# mcu.net
KiCad netlist of a schematic drawn in Altium Designer
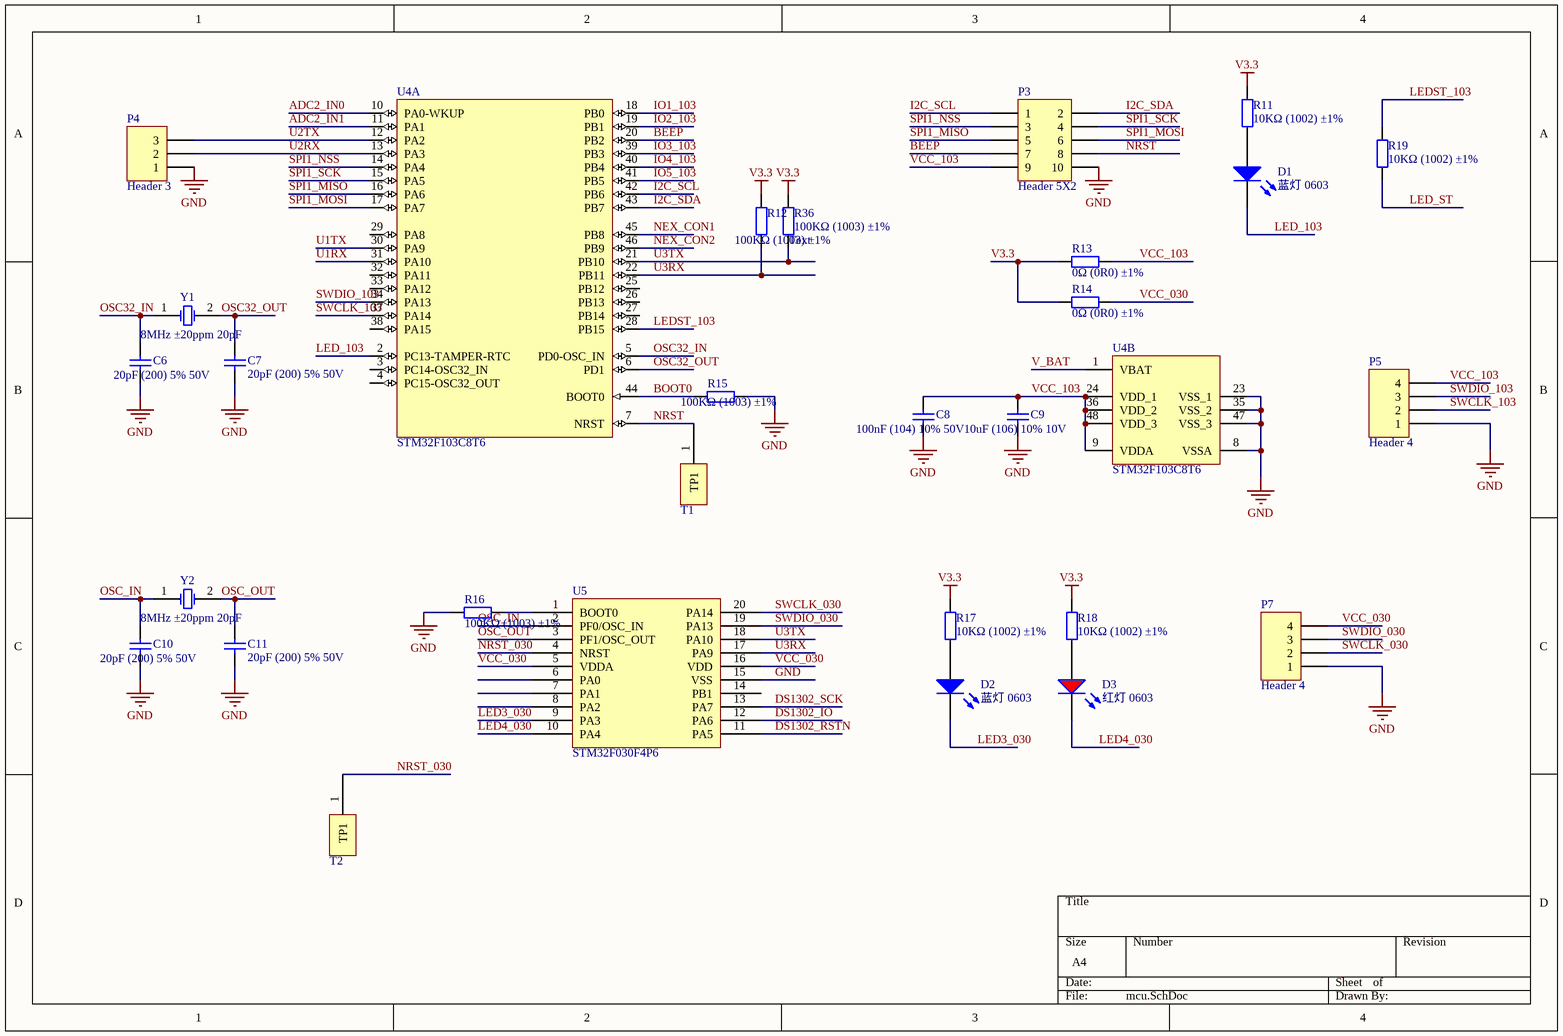
[diagram p0: mcu.SchDoc]

(export (version "E")
  (design (tool "Eeschema 10.0.6"))
  (components
    (comp (ref "C6")
      (value "20pF (200) 5% 50V")
      (footprint "0603_C")
      (description "贴片电容")
      (libsource (lib "Miscellaneous Devices LC") (part "0603 20pF (200) 5% 50V"))
    )
    (comp (ref "C7")
      (value "20pF (200) 5% 50V")
      (footprint "0603_C")
      (description "贴片电容")
      (libsource (lib "Miscellaneous Devices LC") (part "0603 20pF (200) 5% 50V"))
    )
    (comp (ref "C8")
      (value "100nF (104) 10% 50V")
      (footprint "0603_C")
      (description "贴片电容")
      (libsource (lib "Miscellaneous Devices LC") (part "0603 100nF (104) 10% 50V"))
    )
    (comp (ref "C9")
      (value "10uF (106) 10% 10V")
      (footprint "0603_C")
      (description "贴片电容")
      (libsource (lib "Miscellaneous Devices LC") (part "0603 10uF (106) 10% 10V"))
    )
    (comp (ref "C10")
      (value "20pF (200) 5% 50V")
      (footprint "0603_C")
      (description "贴片电容")
      (libsource (lib "Miscellaneous Devices LC") (part "0603 20pF (200) 5% 50V"))
    )
    (comp (ref "C11")
      (value "20pF (200) 5% 50V")
      (footprint "0603_C")
      (description "贴片电容")
      (libsource (lib "Miscellaneous Devices LC") (part "0603 20pF (200) 5% 50V"))
    )
    (comp (ref "D1")
      (value "蓝灯 0603")
      (footprint "0603_LED_S1")
      (description "发光二极管")
      (libsource (lib "Miscellaneous Devices LC") (part "0603 蓝灯"))
    )
    (comp (ref "D2")
      (value "蓝灯 0603")
      (footprint "0603_LED_S1")
      (description "发光二极管")
      (libsource (lib "Miscellaneous Devices LC") (part "0603 蓝灯"))
    )
    (comp (ref "D3")
      (value "红灯 0603")
      (footprint "0603_LED_S1")
      (description "发光二极管")
      (libsource (lib "Miscellaneous Devices LC") (part "0603 红灯"))
    )
    (comp (ref "P3")
      (value "Header 5X2")
      (footprint "HDR2X5")
      (description "Header, 5-Pin, Dual row")
      (fields (field (name "PUBLISHER") "Altium Limited"))
      (libsource (lib "Miscellaneous Connectors") (part "Header 5X2"))
    )
    (comp (ref "P4")
      (value "Header 3")
      (footprint "HDR1X3")
      (description "Header, 3-Pin")
      (fields (field (name "PUBLISHER") "Altium Limited"))
      (libsource (lib "Miscellaneous Connectors") (part "Header 3"))
    )
    (comp (ref "P5")
      (value "Header 4")
      (footprint "HDR1X4")
      (description "Header, 4-Pin")
      (fields (field (name "PUBLISHER") "Altium Limited"))
      (libsource (lib "Miscellaneous Connectors") (part "Header 4"))
    )
    (comp (ref "P7")
      (value "Header 4")
      (footprint "HDR1X4")
      (description "Header, 4-Pin")
      (fields (field (name "PUBLISHER") "Altium Limited"))
      (libsource (lib "Miscellaneous Connectors") (part "Header 4"))
    )
    (comp (ref "R11")
      (value "10KΩ (1002) ±1%")
      (footprint "0603_R")
      (description "贴片电阻")
      (libsource (lib "Miscellaneous Devices LC") (part "0603 10KΩ (1002) 1%"))
    )
    (comp (ref "R12")
      (value "100KΩ (1003) ±1%")
      (footprint "0603_R")
      (description "贴片电阻")
      (libsource (lib "") (part "0603 100KΩ (1003) 1%_1"))
    )
    (comp (ref "R13")
      (value "0Ω (0R0) ±1%")
      (footprint "1206_R")
      (description "贴片电阻")
      (libsource (lib "Miscellaneous Devices LC") (part "1206 0Ω (0R0) 1%"))
    )
    (comp (ref "R14")
      (value "0Ω (0R0) ±1%")
      (footprint "1206_R")
      (description "贴片电阻")
      (libsource (lib "Miscellaneous Devices LC") (part "1206 0Ω (0R0) 1%"))
    )
    (comp (ref "R15")
      (value "100KΩ (1003) ±1%")
      (footprint "0603_R")
      (description "贴片电阻")
      (libsource (lib "Miscellaneous Devices LC") (part "0603 100KΩ (1003) 1%"))
    )
    (comp (ref "R16")
      (value "100KΩ (1003) ±1%")
      (footprint "0603_R")
      (description "贴片电阻")
      (libsource (lib "Miscellaneous Devices LC") (part "0603 100KΩ (1003) 1%"))
    )
    (comp (ref "R17")
      (value "10KΩ (1002) ±1%")
      (footprint "0603_R")
      (description "贴片电阻")
      (libsource (lib "Miscellaneous Devices LC") (part "0603 10KΩ (1002) 1%"))
    )
    (comp (ref "R18")
      (value "10KΩ (1002) ±1%")
      (footprint "0603_R")
      (description "贴片电阻")
      (libsource (lib "Miscellaneous Devices LC") (part "0603 10KΩ (1002) 1%"))
    )
    (comp (ref "R19")
      (value "10KΩ (1002) ±1%")
      (footprint "0603_R")
      (description "贴片电阻")
      (libsource (lib "Miscellaneous Devices LC") (part "0603 10KΩ (1002) 1%"))
    )
    (comp (ref "R36")
      (value "100KΩ (1003) ±1%")
      (footprint "0603_R")
      (description "贴片电阻")
      (libsource (lib "") (part "0603 100KΩ (1003) 1%_1"))
    )
    (comp (ref "T1") (value "TP1") (footprint "TP1") (libsource (lib "CHK-I") (part "TP1")))
    (comp (ref "T2") (value "TP1") (footprint "TP1") (libsource (lib "CHK-I") (part "TP1")))
    (comp (ref "U4")
      (value "STM32F103C8T6")
      (footprint "LQFP-48_7x7x05P")
      (description "ARM")
      (libsource (lib "Miscellaneous Devices LC") (part "STM32F103C8T6"))
    )
    (comp (ref "U5")
      (value "STM32F030F4P6")
      (footprint "TSSOP-20")
      (description "ARM")
      (libsource (lib "Miscellaneous Devices LC") (part "STM32F030F4P6"))
    )
    (comp (ref "Y1")
      (value "8MHz ±20ppm 20pF")
      (footprint "SMD-5032_2P")
      (description "贴片晶振")
      (libsource (lib "Miscellaneous Devices LC") (part "SMD-5032_2P 8MHz 20ppm 20pF"))
    )
    (comp (ref "Y2")
      (value "8MHz ±20ppm 20pF")
      (footprint "SMD-5032_2P")
      (description "贴片晶振")
      (libsource (lib "Miscellaneous Devices LC") (part "SMD-5032_2P 8MHz 20ppm 20pF"))
    )
  )
  (nets
    (net (code "1") (name "/ADC2_IN0") (class "Default")
      (node (ref "U4") (pin "10") (pinfunction "PA0-WKUP_10") (pintype "bidirectional"))
    )
    (net (code "2") (name "/ADC2_IN1") (class "Default")
      (node (ref "U4") (pin "11") (pinfunction "PA1_11") (pintype "bidirectional"))
    )
    (net (code "3") (name "/BEEP") (class "Default")
      (node (ref "P3") (pin "7") (pinfunction "7_7") (pintype "passive"))
      (node (ref "U4") (pin "20") (pinfunction "PB2_20") (pintype "bidirectional"))
    )
    (net (code "4") (name "/BOOT0") (class "Default")
      (node (ref "R15") (pin "1") (pinfunction "1_1") (pintype "passive"))
      (node (ref "U4") (pin "44") (pinfunction "BOOT0_44") (pintype "input"))
    )
    (net (code "5") (name "/DS1302_IO") (class "Default")
      (node (ref "U5") (pin "12") (pinfunction "PA6_12") (pintype "passive"))
    )
    (net (code "6") (name "/DS1302_RSTN") (class "Default")
      (node (ref "U5") (pin "11") (pinfunction "PA5_11") (pintype "passive"))
    )
    (net (code "7") (name "/DS1302_SCK") (class "Default")
      (node (ref "U5") (pin "13") (pinfunction "PA7_13") (pintype "passive"))
    )
    (net (code "8") (name "/I2C_SCL") (class "Default")
      (node (ref "P3") (pin "1") (pinfunction "1_1") (pintype "passive"))
      (node (ref "U4") (pin "42") (pinfunction "PB6_42") (pintype "bidirectional"))
    )
    (net (code "9") (name "/I2C_SDA") (class "Default")
      (node (ref "P3") (pin "2") (pinfunction "2_2") (pintype "passive"))
      (node (ref "U4") (pin "43") (pinfunction "PB7_43") (pintype "bidirectional"))
    )
    (net (code "10") (name "/IO1_103") (class "Default")
      (node (ref "U4") (pin "18") (pinfunction "PB0_18") (pintype "bidirectional"))
    )
    (net (code "11") (name "/IO2_103") (class "Default")
      (node (ref "U4") (pin "19") (pinfunction "PB1_19") (pintype "bidirectional"))
    )
    (net (code "12") (name "/IO3_103") (class "Default")
      (node (ref "U4") (pin "39") (pinfunction "PB3_39") (pintype "bidirectional"))
    )
    (net (code "13") (name "/IO4_103") (class "Default")
      (node (ref "U4") (pin "40") (pinfunction "PB4_40") (pintype "bidirectional"))
    )
    (net (code "14") (name "/IO5_103") (class "Default")
      (node (ref "U4") (pin "41") (pinfunction "PB5_41") (pintype "bidirectional"))
    )
    (net (code "15") (name "/LED3_030") (class "Default")
      (node (ref "D2") (pin "K") (pinfunction "K_K") (pintype "passive"))
      (node (ref "U5") (pin "9") (pinfunction "PA3_9") (pintype "passive"))
    )
    (net (code "16") (name "/LED4_030") (class "Default")
      (node (ref "D3") (pin "K") (pinfunction "K_K") (pintype "passive"))
      (node (ref "U5") (pin "10") (pinfunction "PA4_10") (pintype "passive"))
    )
    (net (code "17") (name "/LEDST_103") (class "Default")
      (node (ref "R19") (pin "2") (pinfunction "2_2") (pintype "passive"))
      (node (ref "U4") (pin "28") (pinfunction "PB15_28") (pintype "bidirectional"))
    )
    (net (code "18") (name "/LED_103") (class "Default")
      (node (ref "D1") (pin "K") (pinfunction "K_K") (pintype "passive"))
      (node (ref "U4") (pin "2") (pinfunction "PC13-TAMPER-RTC_2") (pintype "bidirectional"))
    )
    (net (code "19") (name "/LED_ST") (class "Default")
      (node (ref "R19") (pin "1") (pinfunction "1_1") (pintype "passive"))
    )
    (net (code "20") (name "/NEX_CON1") (class "Default")
      (node (ref "U4") (pin "45") (pinfunction "PB8_45") (pintype "bidirectional"))
    )
    (net (code "21") (name "/NEX_CON2") (class "Default")
      (node (ref "U4") (pin "46") (pinfunction "PB9_46") (pintype "bidirectional"))
    )
    (net (code "22") (name "/NRST") (class "Default")
      (node (ref "P3") (pin "8") (pinfunction "8_8") (pintype "passive"))
      (node (ref "T1") (pin "1") (pinfunction "TP1_1") (pintype "passive"))
      (node (ref "U4") (pin "7") (pinfunction "NRST_7") (pintype "bidirectional"))
    )
    (net (code "23") (name "/NRST_030") (class "Default")
      (node (ref "T2") (pin "1") (pinfunction "TP1_1") (pintype "passive"))
      (node (ref "U5") (pin "4") (pinfunction "NRST_4") (pintype "passive"))
    )
    (net (code "24") (name "/OSC32_IN") (class "Default")
      (node (ref "C6") (pin "2") (pinfunction "2_2") (pintype "passive"))
      (node (ref "U4") (pin "5") (pinfunction "PD0-OSC_IN_5") (pintype "bidirectional"))
      (node (ref "Y1") (pin "1") (pinfunction "OSC1_1") (pintype "passive"))
    )
    (net (code "25") (name "/OSC32_OUT") (class "Default")
      (node (ref "C7") (pin "2") (pinfunction "2_2") (pintype "passive"))
      (node (ref "U4") (pin "6") (pinfunction "PD1_6") (pintype "bidirectional"))
      (node (ref "Y1") (pin "2") (pinfunction "OSC2_2") (pintype "passive"))
    )
    (net (code "26") (name "/OSC_IN") (class "Default")
      (node (ref "C10") (pin "2") (pinfunction "2_2") (pintype "passive"))
      (node (ref "U5") (pin "2") (pinfunction "PF0/OSC_IN_2") (pintype "passive"))
      (node (ref "Y2") (pin "1") (pinfunction "OSC1_1") (pintype "passive"))
    )
    (net (code "27") (name "/OSC_OUT") (class "Default")
      (node (ref "C11") (pin "2") (pinfunction "2_2") (pintype "passive"))
      (node (ref "U5") (pin "3") (pinfunction "PF1/OSC_OUT_3") (pintype "passive"))
      (node (ref "Y2") (pin "2") (pinfunction "OSC2_2") (pintype "passive"))
    )
    (net (code "28") (name "/SPI1_MISO") (class "Default")
      (node (ref "P3") (pin "5") (pinfunction "5_5") (pintype "passive"))
      (node (ref "U4") (pin "16") (pinfunction "PA6_16") (pintype "bidirectional"))
    )
    (net (code "29") (name "/SPI1_MOSI") (class "Default")
      (node (ref "P3") (pin "6") (pinfunction "6_6") (pintype "passive"))
      (node (ref "U4") (pin "17") (pinfunction "PA7_17") (pintype "bidirectional"))
    )
    (net (code "30") (name "/SPI1_NSS") (class "Default")
      (node (ref "P3") (pin "3") (pinfunction "3_3") (pintype "passive"))
      (node (ref "U4") (pin "14") (pinfunction "PA4_14") (pintype "bidirectional"))
    )
    (net (code "31") (name "/SPI1_SCK") (class "Default")
      (node (ref "P3") (pin "4") (pinfunction "4_4") (pintype "passive"))
      (node (ref "U4") (pin "15") (pinfunction "PA5_15") (pintype "bidirectional"))
    )
    (net (code "32") (name "/SWCLK_030") (class "Default")
      (node (ref "P7") (pin "2") (pinfunction "2_2") (pintype "passive"))
      (node (ref "U5") (pin "20") (pinfunction "PA14_20") (pintype "passive"))
    )
    (net (code "33") (name "/SWCLK_103") (class "Default")
      (node (ref "P5") (pin "2") (pinfunction "2_2") (pintype "passive"))
      (node (ref "U4") (pin "37") (pinfunction "PA14_37") (pintype "bidirectional"))
    )
    (net (code "34") (name "/SWDIO_030") (class "Default")
      (node (ref "P7") (pin "3") (pinfunction "3_3") (pintype "passive"))
      (node (ref "U5") (pin "19") (pinfunction "PA13_19") (pintype "passive"))
    )
    (net (code "35") (name "/SWDIO_103") (class "Default")
      (node (ref "P5") (pin "3") (pinfunction "3_3") (pintype "passive"))
      (node (ref "U4") (pin "34") (pinfunction "PA13_34") (pintype "bidirectional"))
    )
    (net (code "36") (name "/U1RX") (class "Default")
      (node (ref "U4") (pin "31") (pinfunction "PA10_31") (pintype "bidirectional"))
    )
    (net (code "37") (name "/U1TX") (class "Default")
      (node (ref "U4") (pin "30") (pinfunction "PA9_30") (pintype "bidirectional"))
    )
    (net (code "38") (name "/U2RX") (class "Default")
      (node (ref "P4") (pin "2") (pinfunction "2_2") (pintype "passive"))
      (node (ref "U4") (pin "13") (pinfunction "PA3_13") (pintype "bidirectional"))
    )
    (net (code "39") (name "/U2TX") (class "Default")
      (node (ref "P4") (pin "3") (pinfunction "3_3") (pintype "passive"))
      (node (ref "U4") (pin "12") (pinfunction "PA2_12") (pintype "bidirectional"))
    )
    (net (code "40") (name "/U3RX") (class "Default")
      (node (ref "R12") (pin "1") (pinfunction "1_1") (pintype "passive"))
      (node (ref "U4") (pin "22") (pinfunction "PB11_22") (pintype "bidirectional"))
      (node (ref "U5") (pin "17") (pinfunction "PA9_17") (pintype "passive"))
    )
    (net (code "41") (name "/U3TX") (class "Default")
      (node (ref "R36") (pin "1") (pinfunction "1_1") (pintype "passive"))
      (node (ref "U4") (pin "21") (pinfunction "PB10_21") (pintype "bidirectional"))
      (node (ref "U5") (pin "18") (pinfunction "PA10_18") (pintype "passive"))
    )
    (net (code "42") (name "/VCC_030") (class "Default")
      (node (ref "P7") (pin "4") (pinfunction "4_4") (pintype "passive"))
      (node (ref "R14") (pin "2") (pinfunction "2_2") (pintype "passive"))
      (node (ref "U5") (pin "16") (pinfunction "VDD_16") (pintype "passive"))
      (node (ref "U5") (pin "5") (pinfunction "VDDA_5") (pintype "passive"))
    )
    (net (code "43") (name "/VCC_103") (class "Default")
      (node (ref "C8") (pin "2") (pinfunction "2_2") (pintype "passive"))
      (node (ref "C9") (pin "1") (pinfunction "1_1") (pintype "passive"))
      (node (ref "P3") (pin "9") (pinfunction "9_9") (pintype "passive"))
      (node (ref "P5") (pin "4") (pinfunction "4_4") (pintype "passive"))
      (node (ref "R13") (pin "2") (pinfunction "2_2") (pintype "passive"))
      (node (ref "U4") (pin "24") (pinfunction "VDD_1_24") (pintype "power_in"))
      (node (ref "U4") (pin "36") (pinfunction "VDD_2_36") (pintype "power_in"))
      (node (ref "U4") (pin "48") (pinfunction "VDD_3_48") (pintype "power_in"))
      (node (ref "U4") (pin "9") (pinfunction "VDDA_9") (pintype "power_in"))
    )
    (net (code "44") (name "/V_BAT") (class "Default")
      (node (ref "U4") (pin "1") (pinfunction "VBAT_1") (pintype "power_in"))
    )
    (net (code "45") (name "GND") (class "Default")
      (node (ref "C10") (pin "1") (pinfunction "1_1") (pintype "passive"))
      (node (ref "C11") (pin "1") (pinfunction "1_1") (pintype "passive"))
      (node (ref "C6") (pin "1") (pinfunction "1_1") (pintype "passive"))
      (node (ref "C7") (pin "1") (pinfunction "1_1") (pintype "passive"))
      (node (ref "C8") (pin "1") (pinfunction "1_1") (pintype "passive"))
      (node (ref "C9") (pin "2") (pinfunction "2_2") (pintype "passive"))
      (node (ref "P3") (pin "10") (pinfunction "10_10") (pintype "passive"))
      (node (ref "P4") (pin "1") (pinfunction "1_1") (pintype "passive"))
      (node (ref "P5") (pin "1") (pinfunction "1_1") (pintype "passive"))
      (node (ref "P7") (pin "1") (pinfunction "1_1") (pintype "passive"))
      (node (ref "R15") (pin "2") (pinfunction "2_2") (pintype "passive"))
      (node (ref "R16") (pin "1") (pinfunction "1_1") (pintype "passive"))
      (node (ref "U4") (pin "23") (pinfunction "VSS_1_23") (pintype "power_in"))
      (node (ref "U4") (pin "35") (pinfunction "VSS_2_35") (pintype "power_in"))
      (node (ref "U4") (pin "47") (pinfunction "VSS_3_47") (pintype "power_in"))
      (node (ref "U4") (pin "8") (pinfunction "VSSA_8") (pintype "power_in"))
      (node (ref "U5") (pin "15") (pinfunction "VSS_15") (pintype "passive"))
    )
    (net (code "46") (name "Net-(D1-PadA)") (class "Default")
      (node (ref "D1") (pin "A") (pinfunction "A_A") (pintype "passive"))
      (node (ref "R11") (pin "1") (pinfunction "1_1") (pintype "passive"))
    )
    (net (code "47") (name "Net-(D2-PadA)") (class "Default")
      (node (ref "D2") (pin "A") (pinfunction "A_A") (pintype "passive"))
      (node (ref "R17") (pin "1") (pinfunction "1_1") (pintype "passive"))
    )
    (net (code "48") (name "Net-(D3-PadA)") (class "Default")
      (node (ref "D3") (pin "A") (pinfunction "A_A") (pintype "passive"))
      (node (ref "R18") (pin "1") (pinfunction "1_1") (pintype "passive"))
    )
    (net (code "49") (name "Net-(U5-BOOT0)") (class "Default")
      (node (ref "R16") (pin "2") (pinfunction "2_2") (pintype "passive"))
      (node (ref "U5") (pin "1") (pinfunction "BOOT0_1") (pintype "passive"))
    )
    (net (code "50") (name "V3.3") (class "Default")
      (node (ref "R11") (pin "2") (pinfunction "2_2") (pintype "passive"))
      (node (ref "R12") (pin "2") (pinfunction "2_2") (pintype "passive"))
      (node (ref "R13") (pin "1") (pinfunction "1_1") (pintype "passive"))
      (node (ref "R14") (pin "1") (pinfunction "1_1") (pintype "passive"))
      (node (ref "R17") (pin "2") (pinfunction "2_2") (pintype "passive"))
      (node (ref "R18") (pin "2") (pinfunction "2_2") (pintype "passive"))
      (node (ref "R36") (pin "2") (pinfunction "2_2") (pintype "passive"))
    )
    (net (code "51") (name "unconnected-(U4A-PA8-Pad29)") (class "Default")
      (node (ref "U4") (pin "29") (pinfunction "PA8_29") (pintype "bidirectional"))
    )
    (net (code "52") (name "unconnected-(U4A-PA11-Pad32)") (class "Default")
      (node (ref "U4") (pin "32") (pinfunction "PA11_32") (pintype "bidirectional"))
    )
    (net (code "53") (name "unconnected-(U4A-PA12-Pad33)") (class "Default")
      (node (ref "U4") (pin "33") (pinfunction "PA12_33") (pintype "bidirectional"))
    )
    (net (code "54") (name "unconnected-(U4A-PA15-Pad38)") (class "Default")
      (node (ref "U4") (pin "38") (pinfunction "PA15_38") (pintype "bidirectional"))
    )
    (net (code "55") (name "unconnected-(U4A-PB12-Pad25)") (class "Default")
      (node (ref "U4") (pin "25") (pinfunction "PB12_25") (pintype "bidirectional"))
    )
    (net (code "56") (name "unconnected-(U4A-PB13-Pad26)") (class "Default")
      (node (ref "U4") (pin "26") (pinfunction "PB13_26") (pintype "bidirectional"))
    )
    (net (code "57") (name "unconnected-(U4A-PB14-Pad27)") (class "Default")
      (node (ref "U4") (pin "27") (pinfunction "PB14_27") (pintype "bidirectional"))
    )
    (net (code "58") (name "unconnected-(U4A-PC14-OSC32_IN-Pad3)") (class "Default")
      (node (ref "U4") (pin "3") (pinfunction "PC14-OSC32_IN_3") (pintype "bidirectional"))
    )
    (net (code "59") (name "unconnected-(U4A-PC15-OSC32_OUT-Pad4)") (class "Default")
      (node (ref "U4") (pin "4") (pinfunction "PC15-OSC32_OUT_4") (pintype "bidirectional"))
    )
    (net (code "60") (name "unconnected-(U5-PA0-Pad6)") (class "Default")
      (node (ref "U5") (pin "6") (pinfunction "PA0_6") (pintype "passive"))
    )
    (net (code "61") (name "unconnected-(U5-PA1-Pad7)") (class "Default")
      (node (ref "U5") (pin "7") (pinfunction "PA1_7") (pintype "passive"))
    )
    (net (code "62") (name "unconnected-(U5-PA2-Pad8)") (class "Default")
      (node (ref "U5") (pin "8") (pinfunction "PA2_8") (pintype "passive"))
    )
    (net (code "63") (name "unconnected-(U5-PB1-Pad14)") (class "Default")
      (node (ref "U5") (pin "14") (pinfunction "PB1_14") (pintype "passive"))
    )
  )
)
